# Sheet1.net
KiCad netlist of a schematic drawn in Altium Designer
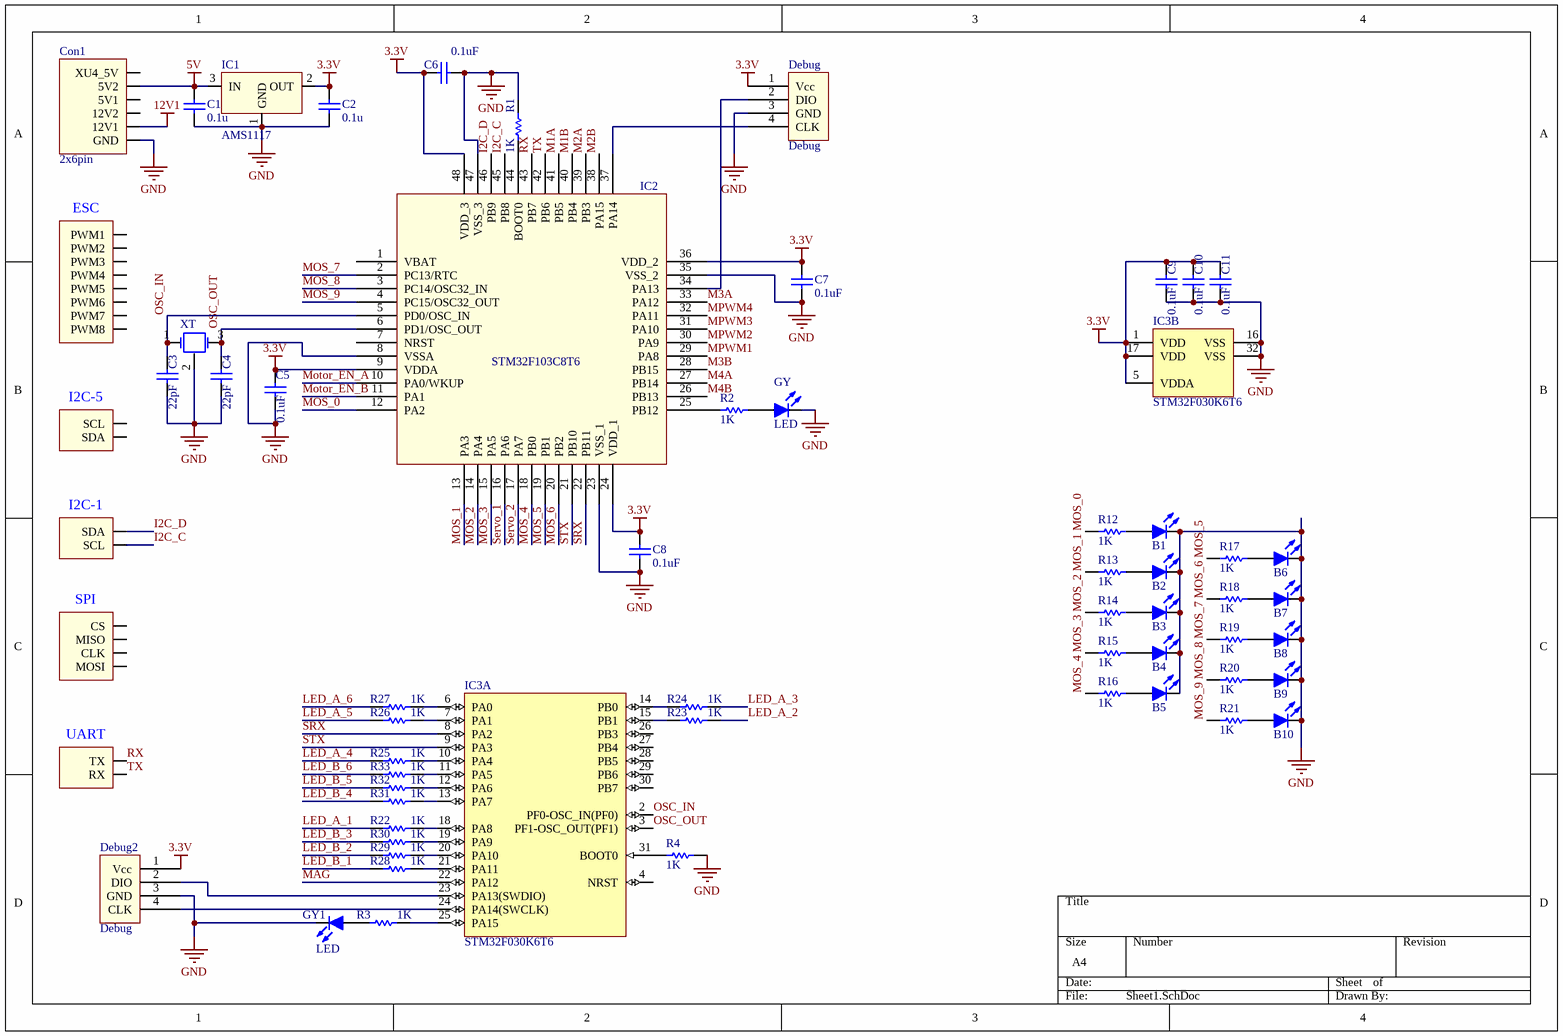
[diagram p0: Sheet1.SchDoc]

(export (version "E")
  (design (tool "Eeschema 10.0.6"))
  (components
    (comp (ref "B1") (value "LED") (footprint "LED-0805") (libsource (lib "MyOwnSchlib_ver1.2") (part "LED")))
    (comp (ref "B2") (value "LED") (footprint "LED-0805") (libsource (lib "MyOwnSchlib_ver1.2") (part "LED")))
    (comp (ref "B3") (value "LED") (footprint "LED-0805") (libsource (lib "MyOwnSchlib_ver1.2") (part "LED")))
    (comp (ref "B4") (value "LED") (footprint "LED-0805") (libsource (lib "MyOwnSchlib_ver1.2") (part "LED")))
    (comp (ref "B5") (value "LED") (footprint "LED-0805") (libsource (lib "MyOwnSchlib_ver1.2") (part "LED")))
    (comp (ref "B6") (value "LED") (footprint "LED-0805") (libsource (lib "MyOwnSchlib_ver1.2") (part "LED")))
    (comp (ref "B7") (value "LED") (footprint "LED-0805") (libsource (lib "MyOwnSchlib_ver1.2") (part "LED")))
    (comp (ref "B8") (value "LED") (footprint "LED-0805") (libsource (lib "MyOwnSchlib_ver1.2") (part "LED")))
    (comp (ref "B9") (value "LED") (footprint "LED-0805") (libsource (lib "MyOwnSchlib_ver1.2") (part "LED")))
    (comp (ref "B10")
      (value "LED")
      (footprint "LED-0805")
      (libsource (lib "MyOwnSchlib_ver1.2") (part "LED"))
    )
    (comp (ref "C1") (value "0.1u") (footprint "C0805") (libsource (lib "MyOwnSchlib_ver1.2") (part "Cap")))
    (comp (ref "C2") (value "0.1u") (footprint "C0805") (libsource (lib "MyOwnSchlib_ver1.2") (part "Cap")))
    (comp (ref "C3") (value "22pF") (footprint "C0805") (libsource (lib "Schlib2") (part "Capacitor")))
    (comp (ref "C4") (value "22pF") (footprint "C0805") (libsource (lib "Schlib2") (part "Capacitor")))
    (comp (ref "C5") (value "0.1uF") (footprint "C0805") (libsource (lib "Schlib2") (part "Capacitor")))
    (comp (ref "C6") (value "0.1uF") (footprint "C0805") (libsource (lib "Schlib2") (part "Capacitor")))
    (comp (ref "C7") (value "0.1uF") (footprint "C0805") (libsource (lib "Schlib2") (part "Capacitor")))
    (comp (ref "C8") (value "0.1uF") (footprint "C0805") (libsource (lib "Schlib2") (part "Capacitor")))
    (comp (ref "C9") (value "0.1uF") (footprint "C0805") (libsource (lib "MyOwnSchlib_ver1.2") (part "Cap")))
    (comp (ref "C10") (value "0.1uF") (footprint "C0805") (libsource (lib "MyOwnSchlib_ver1.2") (part "Cap")))
    (comp (ref "C11") (value "0.1uF") (footprint "C0805") (libsource (lib "MyOwnSchlib_ver1.2") (part "Cap")))
    (comp (ref "Con1") (value "2x6pin") (footprint "2x6pin") (libsource (lib "Schlib1") (part "2x6pin")))
    (comp (ref "Con2") (value "2x10pin") (footprint "2x10pin") (libsource (lib "Schlib1") (part "2x10pin")))
    (comp (ref "Debug")
      (value "Debug")
      (footprint "Debug_SMD")
      (libsource (lib "MyOwnSchlib_ver1.2") (part "Debug"))
    )
    (comp (ref "Debug2") (value "Debug") (footprint "Debug_SMD") (libsource (lib "") (part "Debug_1")))
    (comp (ref "GY") (value "LED") (footprint "LED-0805") (libsource (lib "MyOwnSchlib_ver1.2") (part "LED")))
    (comp (ref "GY1")
      (value "LED")
      (footprint "LED-0805")
      (libsource (lib "MyOwnSchlib_ver1.2") (part "LED"))
    )
    (comp (ref "IC1")
      (value "AMS1117")
      (footprint "SOT-223")
      (libsource (lib "MyOwnSchlib_ver1.2") (part "AMS1117"))
    )
    (comp (ref "IC2")
      (value "STM32F103C8T6")
      (footprint "LQFP48")
      (libsource (lib "Schlib2") (part "STM32F103C8T6"))
    )
    (comp (ref "IC3")
      (value "STM32F030K6T6")
      (footprint "LQFP-32")
      (libsource (lib "STMicroelectronics STM32 F0") (part "STM32F030K6T6"))
    )
    (comp (ref "R1") (value "1K") (footprint "R0805") (libsource (lib "Schlib2") (part "Resistor")))
    (comp (ref "R2")
      (value "1K")
      (footprint "R0805")
      (libsource (lib "MyOwnSchlib_ver1.2") (part "Resistor"))
    )
    (comp (ref "R3")
      (value "1K")
      (footprint "R0805")
      (libsource (lib "MyOwnSchlib_ver1.2") (part "Resistor"))
    )
    (comp (ref "R4")
      (value "1K")
      (footprint "R0805")
      (libsource (lib "MyOwnSchlib_ver1.2") (part "Resistor"))
    )
    (comp (ref "R12")
      (value "1K")
      (footprint "R0805")
      (libsource (lib "MyOwnSchlib_ver1.2") (part "Resistor"))
    )
    (comp (ref "R13")
      (value "1K")
      (footprint "R0805")
      (libsource (lib "MyOwnSchlib_ver1.2") (part "Resistor"))
    )
    (comp (ref "R14")
      (value "1K")
      (footprint "R0805")
      (libsource (lib "MyOwnSchlib_ver1.2") (part "Resistor"))
    )
    (comp (ref "R15")
      (value "1K")
      (footprint "R0805")
      (libsource (lib "MyOwnSchlib_ver1.2") (part "Resistor"))
    )
    (comp (ref "R16")
      (value "1K")
      (footprint "R0805")
      (libsource (lib "MyOwnSchlib_ver1.2") (part "Resistor"))
    )
    (comp (ref "R17")
      (value "1K")
      (footprint "R0805")
      (libsource (lib "MyOwnSchlib_ver1.2") (part "Resistor"))
    )
    (comp (ref "R18")
      (value "1K")
      (footprint "R0805")
      (libsource (lib "MyOwnSchlib_ver1.2") (part "Resistor"))
    )
    (comp (ref "R19")
      (value "1K")
      (footprint "R0805")
      (libsource (lib "MyOwnSchlib_ver1.2") (part "Resistor"))
    )
    (comp (ref "R20")
      (value "1K")
      (footprint "R0805")
      (libsource (lib "MyOwnSchlib_ver1.2") (part "Resistor"))
    )
    (comp (ref "R21")
      (value "1K")
      (footprint "R0805")
      (libsource (lib "MyOwnSchlib_ver1.2") (part "Resistor"))
    )
    (comp (ref "R22")
      (value "1K")
      (footprint "R0805")
      (libsource (lib "MyOwnSchlib_ver1.2") (part "Resistor"))
    )
    (comp (ref "R23")
      (value "1K")
      (footprint "R0805")
      (libsource (lib "MyOwnSchlib_ver1.2") (part "Resistor"))
    )
    (comp (ref "R24")
      (value "1K")
      (footprint "R0805")
      (libsource (lib "MyOwnSchlib_ver1.2") (part "Resistor"))
    )
    (comp (ref "R25")
      (value "1K")
      (footprint "R0805")
      (libsource (lib "MyOwnSchlib_ver1.2") (part "Resistor"))
    )
    (comp (ref "R26")
      (value "1K")
      (footprint "R0805")
      (libsource (lib "MyOwnSchlib_ver1.2") (part "Resistor"))
    )
    (comp (ref "R27")
      (value "1K")
      (footprint "R0805")
      (libsource (lib "MyOwnSchlib_ver1.2") (part "Resistor"))
    )
    (comp (ref "R28")
      (value "1K")
      (footprint "R0805")
      (libsource (lib "MyOwnSchlib_ver1.2") (part "Resistor"))
    )
    (comp (ref "R29")
      (value "1K")
      (footprint "R0805")
      (libsource (lib "MyOwnSchlib_ver1.2") (part "Resistor"))
    )
    (comp (ref "R30")
      (value "1K")
      (footprint "R0805")
      (libsource (lib "MyOwnSchlib_ver1.2") (part "Resistor"))
    )
    (comp (ref "R31")
      (value "1K")
      (footprint "R0805")
      (libsource (lib "MyOwnSchlib_ver1.2") (part "Resistor"))
    )
    (comp (ref "R32")
      (value "1K")
      (footprint "R0805")
      (libsource (lib "MyOwnSchlib_ver1.2") (part "Resistor"))
    )
    (comp (ref "R33")
      (value "1K")
      (footprint "R0805")
      (libsource (lib "MyOwnSchlib_ver1.2") (part "Resistor"))
    )
    (comp (ref "XT") (value "8MHz") (footprint "3225-P") (libsource (lib "Schlib2") (part "Passive Crystal")))
  )
  (nets
    (net (code "1") (name "/I2C_C") (class "Default")
      (node (ref "Con2") (pin "14") (pinfunction "SCL_14") (pintype "passive"))
      (node (ref "IC2") (pin "45") (pinfunction "PB8_45") (pintype "passive"))
    )
    (net (code "2") (name "/I2C_D") (class "Default")
      (node (ref "Con2") (pin "13") (pinfunction "SDA_13") (pintype "passive"))
      (node (ref "IC2") (pin "46") (pinfunction "PB9_46") (pintype "passive"))
    )
    (net (code "3") (name "/LED_A_1") (class "Default")
      (node (ref "R22") (pin "1") (pinfunction "1_1") (pintype "passive"))
    )
    (net (code "4") (name "/LED_A_2") (class "Default")
      (node (ref "R23") (pin "2") (pinfunction "2_2") (pintype "passive"))
    )
    (net (code "5") (name "/LED_A_3") (class "Default")
      (node (ref "R24") (pin "2") (pinfunction "2_2") (pintype "passive"))
    )
    (net (code "6") (name "/LED_A_4") (class "Default")
      (node (ref "R25") (pin "1") (pinfunction "1_1") (pintype "passive"))
    )
    (net (code "7") (name "/LED_A_5") (class "Default")
      (node (ref "R26") (pin "1") (pinfunction "1_1") (pintype "passive"))
    )
    (net (code "8") (name "/LED_A_6") (class "Default")
      (node (ref "R27") (pin "1") (pinfunction "1_1") (pintype "passive"))
    )
    (net (code "9") (name "/LED_B_1") (class "Default")
      (node (ref "R28") (pin "1") (pinfunction "1_1") (pintype "passive"))
    )
    (net (code "10") (name "/LED_B_2") (class "Default")
      (node (ref "R29") (pin "1") (pinfunction "1_1") (pintype "passive"))
    )
    (net (code "11") (name "/LED_B_3") (class "Default")
      (node (ref "R30") (pin "1") (pinfunction "1_1") (pintype "passive"))
    )
    (net (code "12") (name "/LED_B_4") (class "Default")
      (node (ref "R31") (pin "1") (pinfunction "1_1") (pintype "passive"))
    )
    (net (code "13") (name "/LED_B_5") (class "Default")
      (node (ref "R32") (pin "1") (pinfunction "1_1") (pintype "passive"))
    )
    (net (code "14") (name "/LED_B_6") (class "Default")
      (node (ref "R33") (pin "1") (pinfunction "1_1") (pintype "passive"))
    )
    (net (code "15") (name "/M1A") (class "Default")
      (node (ref "IC2") (pin "41") (pinfunction "PB5_41") (pintype "passive"))
    )
    (net (code "16") (name "/M1B") (class "Default")
      (node (ref "IC2") (pin "40") (pinfunction "PB4_40") (pintype "passive"))
    )
    (net (code "17") (name "/M2A") (class "Default")
      (node (ref "IC2") (pin "39") (pinfunction "PB3_39") (pintype "passive"))
    )
    (net (code "18") (name "/M2B") (class "Default")
      (node (ref "IC2") (pin "38") (pinfunction "PA15_38") (pintype "passive"))
    )
    (net (code "19") (name "/M3A") (class "Default")
      (node (ref "IC2") (pin "33") (pinfunction "PA12_33") (pintype "passive"))
    )
    (net (code "20") (name "/M3B") (class "Default")
      (node (ref "IC2") (pin "28") (pinfunction "PB15_28") (pintype "passive"))
    )
    (net (code "21") (name "/M4A") (class "Default")
      (node (ref "IC2") (pin "27") (pinfunction "PB14_27") (pintype "passive"))
    )
    (net (code "22") (name "/M4B") (class "Default")
      (node (ref "IC2") (pin "26") (pinfunction "PB13_26") (pintype "passive"))
    )
    (net (code "23") (name "/MAG") (class "Default")
      (node (ref "IC3") (pin "22") (pinfunction "PA12_22") (pintype "bidirectional"))
    )
    (net (code "24") (name "/MOS_0") (class "Default")
      (node (ref "IC2") (pin "12") (pinfunction "PA2_12") (pintype "passive"))
      (node (ref "R12") (pin "1") (pinfunction "1_1") (pintype "passive"))
    )
    (net (code "25") (name "/MOS_1") (class "Default")
      (node (ref "IC2") (pin "13") (pinfunction "PA3_13") (pintype "passive"))
      (node (ref "R13") (pin "1") (pinfunction "1_1") (pintype "passive"))
    )
    (net (code "26") (name "/MOS_2") (class "Default")
      (node (ref "IC2") (pin "14") (pinfunction "PA4_14") (pintype "passive"))
      (node (ref "R14") (pin "1") (pinfunction "1_1") (pintype "passive"))
    )
    (net (code "27") (name "/MOS_3") (class "Default")
      (node (ref "IC2") (pin "15") (pinfunction "PA5_15") (pintype "passive"))
      (node (ref "R15") (pin "1") (pinfunction "1_1") (pintype "passive"))
    )
    (net (code "28") (name "/MOS_4") (class "Default")
      (node (ref "IC2") (pin "18") (pinfunction "PB0_18") (pintype "passive"))
      (node (ref "R16") (pin "1") (pinfunction "1_1") (pintype "passive"))
    )
    (net (code "29") (name "/MOS_5") (class "Default")
      (node (ref "IC2") (pin "19") (pinfunction "PB1_19") (pintype "passive"))
      (node (ref "R17") (pin "1") (pinfunction "1_1") (pintype "passive"))
    )
    (net (code "30") (name "/MOS_6") (class "Default")
      (node (ref "IC2") (pin "20") (pinfunction "PB2_20") (pintype "passive"))
      (node (ref "R18") (pin "1") (pinfunction "1_1") (pintype "passive"))
    )
    (net (code "31") (name "/MOS_7") (class "Default")
      (node (ref "IC2") (pin "2") (pinfunction "PC13/RTC_2") (pintype "passive"))
      (node (ref "R19") (pin "1") (pinfunction "1_1") (pintype "passive"))
    )
    (net (code "32") (name "/MOS_8") (class "Default")
      (node (ref "IC2") (pin "3") (pinfunction "PC14/OSC32_IN_3") (pintype "passive"))
      (node (ref "R20") (pin "1") (pinfunction "1_1") (pintype "passive"))
    )
    (net (code "33") (name "/MOS_9") (class "Default")
      (node (ref "IC2") (pin "4") (pinfunction "PC15/OSC32_OUT_4") (pintype "passive"))
      (node (ref "R21") (pin "1") (pinfunction "1_1") (pintype "passive"))
    )
    (net (code "34") (name "/MPWM1") (class "Default")
      (node (ref "IC2") (pin "29") (pinfunction "PA8_29") (pintype "passive"))
    )
    (net (code "35") (name "/MPWM2") (class "Default")
      (node (ref "IC2") (pin "30") (pinfunction "PA9_30") (pintype "passive"))
    )
    (net (code "36") (name "/MPWM3") (class "Default")
      (node (ref "IC2") (pin "31") (pinfunction "PA10_31") (pintype "passive"))
    )
    (net (code "37") (name "/MPWM4") (class "Default")
      (node (ref "IC2") (pin "32") (pinfunction "PA11_32") (pintype "passive"))
    )
    (net (code "38") (name "/Motor_EN_A") (class "Default")
      (node (ref "IC2") (pin "10") (pinfunction "PA0/WKUP_10") (pintype "passive"))
    )
    (net (code "39") (name "/Motor_EN_B") (class "Default")
      (node (ref "IC2") (pin "11") (pinfunction "PA1_11") (pintype "passive"))
    )
    (net (code "40") (name "/OSC_IN") (class "Default")
      (node (ref "C3") (pin "1") (pinfunction "1_1") (pintype "passive"))
      (node (ref "IC2") (pin "5") (pinfunction "PD0/OSC_IN_5") (pintype "passive"))
      (node (ref "IC3") (pin "2") (pinfunction "PF0-OSC_IN(PF0)_2") (pintype "bidirectional"))
      (node (ref "XT") (pin "1") (pinfunction "OSC1_1") (pintype "passive"))
    )
    (net (code "41") (name "/OSC_OUT") (class "Default")
      (node (ref "C4") (pin "1") (pinfunction "1_1") (pintype "passive"))
      (node (ref "IC2") (pin "6") (pinfunction "PD1/OSC_OUT_6") (pintype "passive"))
      (node (ref "IC3") (pin "3") (pinfunction "PF1-OSC_OUT(PF1)_3") (pintype "bidirectional"))
      (node (ref "XT") (pin "3") (pinfunction "OSC2_3") (pintype "passive"))
    )
    (net (code "42") (name "/RX") (class "Default")
      (node (ref "Con2") (pin "19") (pinfunction "TX_19") (pintype "passive"))
      (node (ref "IC2") (pin "43") (pinfunction "PB7_43") (pintype "passive"))
    )
    (net (code "43") (name "/SRX") (class "Default")
      (node (ref "IC2") (pin "22") (pinfunction "PB11_22") (pintype "passive"))
      (node (ref "IC3") (pin "8") (pinfunction "PA2_8") (pintype "bidirectional"))
    )
    (net (code "44") (name "/STX") (class "Default")
      (node (ref "IC2") (pin "21") (pinfunction "PB10_21") (pintype "passive"))
      (node (ref "IC3") (pin "9") (pinfunction "PA3_9") (pintype "bidirectional"))
    )
    (net (code "45") (name "/Servo_1") (class "Default")
      (node (ref "IC2") (pin "16") (pinfunction "PA6_16") (pintype "passive"))
    )
    (net (code "46") (name "/Servo_2") (class "Default")
      (node (ref "IC2") (pin "17") (pinfunction "PA7_17") (pintype "passive"))
    )
    (net (code "47") (name "/TX") (class "Default")
      (node (ref "Con2") (pin "20") (pinfunction "RX_20") (pintype "passive"))
      (node (ref "IC2") (pin "42") (pinfunction "PB6_42") (pintype "passive"))
    )
    (net (code "48") (name "3.3V") (class "Default")
      (node (ref "C10") (pin "2") (pinfunction "2_2") (pintype "passive"))
      (node (ref "C11") (pin "2") (pinfunction "2_2") (pintype "passive"))
      (node (ref "C2") (pin "2") (pinfunction "2_2") (pintype "passive"))
      (node (ref "C5") (pin "2") (pinfunction "2_2") (pintype "passive"))
      (node (ref "C6") (pin "1") (pinfunction "1_1") (pintype "passive"))
      (node (ref "C7") (pin "2") (pinfunction "2_2") (pintype "passive"))
      (node (ref "C8") (pin "2") (pinfunction "2_2") (pintype "passive"))
      (node (ref "C9") (pin "2") (pinfunction "2_2") (pintype "passive"))
      (node (ref "Debug") (pin "1") (pinfunction "Vcc_1") (pintype "passive"))
      (node (ref "Debug2") (pin "1") (pinfunction "Vcc_1") (pintype "passive"))
      (node (ref "IC1") (pin "2") (pinfunction "OUT_2") (pintype "passive"))
      (node (ref "IC2") (pin "24") (pinfunction "VDD_1_24") (pintype "passive"))
      (node (ref "IC2") (pin "36") (pinfunction "VDD_2_36") (pintype "passive"))
      (node (ref "IC2") (pin "48") (pinfunction "VDD_3_48") (pintype "passive"))
      (node (ref "IC2") (pin "9") (pinfunction "VDDA_9") (pintype "passive"))
      (node (ref "IC3") (pin "1") (pinfunction "VDD_1") (pintype "power_in"))
      (node (ref "IC3") (pin "17") (pinfunction "VDD_17") (pintype "power_in"))
      (node (ref "IC3") (pin "5") (pinfunction "VDDA_5") (pintype "power_in"))
    )
    (net (code "49") (name "5V") (class "Default")
      (node (ref "C1") (pin "2") (pinfunction "2_2") (pintype "passive"))
      (node (ref "Con1") (pin "2") (pinfunction "5V2_2") (pintype "passive"))
      (node (ref "IC1") (pin "3") (pinfunction "IN_3") (pintype "passive"))
    )
    (net (code "50") (name "12V1") (class "Default")
      (node (ref "Con1") (pin "5") (pinfunction "12V1_5") (pintype "passive"))
    )
    (net (code "51") (name "GND") (class "Default")
      (node (ref "B1") (pin "2") (pinfunction "K_2") (pintype "passive"))
      (node (ref "B10") (pin "2") (pinfunction "K_2") (pintype "passive"))
      (node (ref "B2") (pin "2") (pinfunction "K_2") (pintype "passive"))
      (node (ref "B3") (pin "2") (pinfunction "K_2") (pintype "passive"))
      (node (ref "B4") (pin "2") (pinfunction "K_2") (pintype "passive"))
      (node (ref "B5") (pin "2") (pinfunction "K_2") (pintype "passive"))
      (node (ref "B6") (pin "2") (pinfunction "K_2") (pintype "passive"))
      (node (ref "B7") (pin "2") (pinfunction "K_2") (pintype "passive"))
      (node (ref "B8") (pin "2") (pinfunction "K_2") (pintype "passive"))
      (node (ref "B9") (pin "2") (pinfunction "K_2") (pintype "passive"))
      (node (ref "C1") (pin "1") (pinfunction "1_1") (pintype "passive"))
      (node (ref "C10") (pin "1") (pinfunction "1_1") (pintype "passive"))
      (node (ref "C11") (pin "1") (pinfunction "1_1") (pintype "passive"))
      (node (ref "C2") (pin "1") (pinfunction "1_1") (pintype "passive"))
      (node (ref "C3") (pin "2") (pinfunction "2_2") (pintype "passive"))
      (node (ref "C4") (pin "2") (pinfunction "2_2") (pintype "passive"))
      (node (ref "C5") (pin "1") (pinfunction "1_1") (pintype "passive"))
      (node (ref "C6") (pin "2") (pinfunction "2_2") (pintype "passive"))
      (node (ref "C7") (pin "1") (pinfunction "1_1") (pintype "passive"))
      (node (ref "C8") (pin "1") (pinfunction "1_1") (pintype "passive"))
      (node (ref "C9") (pin "1") (pinfunction "1_1") (pintype "passive"))
      (node (ref "Con1") (pin "6") (pinfunction "GND_6") (pintype "passive"))
      (node (ref "Debug") (pin "3") (pinfunction "GND_3") (pintype "passive"))
      (node (ref "Debug2") (pin "3") (pinfunction "GND_3") (pintype "passive"))
      (node (ref "GY") (pin "2") (pinfunction "K_2") (pintype "passive"))
      (node (ref "GY1") (pin "2") (pinfunction "K_2") (pintype "passive"))
      (node (ref "IC1") (pin "1") (pinfunction "GND_1") (pintype "passive"))
      (node (ref "IC2") (pin "23") (pinfunction "VSS_1_23") (pintype "passive"))
      (node (ref "IC2") (pin "35") (pinfunction "VSS_2_35") (pintype "passive"))
      (node (ref "IC2") (pin "47") (pinfunction "VSS_3_47") (pintype "passive"))
      (node (ref "IC2") (pin "8") (pinfunction "VSSA_8") (pintype "passive"))
      (node (ref "IC3") (pin "16") (pinfunction "VSS_16") (pintype "power_in"))
      (node (ref "IC3") (pin "32") (pinfunction "VSS_32") (pintype "power_in"))
      (node (ref "R1") (pin "2") (pinfunction "2_2") (pintype "passive"))
      (node (ref "R4") (pin "2") (pinfunction "2_2") (pintype "passive"))
      (node (ref "XT") (pin "2") (pinfunction "2_2") (pintype "passive"))
    )
    (net (code "52") (name "Net-(B1-A)") (class "Default")
      (node (ref "B1") (pin "1") (pinfunction "A_1") (pintype "passive"))
      (node (ref "R12") (pin "2") (pinfunction "2_2") (pintype "passive"))
    )
    (net (code "53") (name "Net-(B2-A)") (class "Default")
      (node (ref "B2") (pin "1") (pinfunction "A_1") (pintype "passive"))
      (node (ref "R13") (pin "2") (pinfunction "2_2") (pintype "passive"))
    )
    (net (code "54") (name "Net-(B3-A)") (class "Default")
      (node (ref "B3") (pin "1") (pinfunction "A_1") (pintype "passive"))
      (node (ref "R14") (pin "2") (pinfunction "2_2") (pintype "passive"))
    )
    (net (code "55") (name "Net-(B4-A)") (class "Default")
      (node (ref "B4") (pin "1") (pinfunction "A_1") (pintype "passive"))
      (node (ref "R15") (pin "2") (pinfunction "2_2") (pintype "passive"))
    )
    (net (code "56") (name "Net-(B5-A)") (class "Default")
      (node (ref "B5") (pin "1") (pinfunction "A_1") (pintype "passive"))
      (node (ref "R16") (pin "2") (pinfunction "2_2") (pintype "passive"))
    )
    (net (code "57") (name "Net-(B6-A)") (class "Default")
      (node (ref "B6") (pin "1") (pinfunction "A_1") (pintype "passive"))
      (node (ref "R17") (pin "2") (pinfunction "2_2") (pintype "passive"))
    )
    (net (code "58") (name "Net-(B7-A)") (class "Default")
      (node (ref "B7") (pin "1") (pinfunction "A_1") (pintype "passive"))
      (node (ref "R18") (pin "2") (pinfunction "2_2") (pintype "passive"))
    )
    (net (code "59") (name "Net-(B8-A)") (class "Default")
      (node (ref "B8") (pin "1") (pinfunction "A_1") (pintype "passive"))
      (node (ref "R19") (pin "2") (pinfunction "2_2") (pintype "passive"))
    )
    (net (code "60") (name "Net-(B9-A)") (class "Default")
      (node (ref "B9") (pin "1") (pinfunction "A_1") (pintype "passive"))
      (node (ref "R20") (pin "2") (pinfunction "2_2") (pintype "passive"))
    )
    (net (code "61") (name "Net-(B10-A)") (class "Default")
      (node (ref "B10") (pin "1") (pinfunction "A_1") (pintype "passive"))
      (node (ref "R21") (pin "2") (pinfunction "2_2") (pintype "passive"))
    )
    (net (code "62") (name "Net-(Debug-CLK)") (class "Default")
      (node (ref "Debug") (pin "4") (pinfunction "CLK_4") (pintype "passive"))
      (node (ref "IC2") (pin "37") (pinfunction "PA14_37") (pintype "passive"))
    )
    (net (code "63") (name "Net-(Debug-DIO)") (class "Default")
      (node (ref "Debug") (pin "2") (pinfunction "DIO_2") (pintype "passive"))
      (node (ref "IC2") (pin "34") (pinfunction "PA13_34") (pintype "passive"))
    )
    (net (code "64") (name "Net-(Debug2-CLK)") (class "Default")
      (node (ref "Debug2") (pin "4") (pinfunction "CLK_4") (pintype "passive"))
      (node (ref "IC3") (pin "24") (pinfunction "PA14(SWCLK)_24") (pintype "bidirectional"))
    )
    (net (code "65") (name "Net-(Debug2-DIO)") (class "Default")
      (node (ref "Debug2") (pin "2") (pinfunction "DIO_2") (pintype "passive"))
      (node (ref "IC3") (pin "23") (pinfunction "PA13(SWDIO)_23") (pintype "bidirectional"))
    )
    (net (code "66") (name "Net-(GY-A)") (class "Default")
      (node (ref "GY") (pin "1") (pinfunction "A_1") (pintype "passive"))
      (node (ref "R2") (pin "2") (pinfunction "2_2") (pintype "passive"))
    )
    (net (code "67") (name "Net-(GY1-A)") (class "Default")
      (node (ref "GY1") (pin "1") (pinfunction "A_1") (pintype "passive"))
      (node (ref "R3") (pin "1") (pinfunction "1_1") (pintype "passive"))
    )
    (net (code "68") (name "Net-(IC2-BOOT0)") (class "Default")
      (node (ref "IC2") (pin "44") (pinfunction "BOOT0_44") (pintype "passive"))
      (node (ref "R1") (pin "1") (pinfunction "1_1") (pintype "passive"))
    )
    (net (code "69") (name "Net-(IC2-PB12)") (class "Default")
      (node (ref "IC2") (pin "25") (pinfunction "PB12_25") (pintype "passive"))
      (node (ref "R2") (pin "1") (pinfunction "1_1") (pintype "passive"))
    )
    (net (code "70") (name "Net-(IC3A-BOOT0)") (class "Default")
      (node (ref "IC3") (pin "31") (pinfunction "BOOT0_31") (pintype "input"))
      (node (ref "R4") (pin "1") (pinfunction "1_1") (pintype "passive"))
    )
    (net (code "71") (name "Net-(IC3A-PA0)") (class "Default")
      (node (ref "IC3") (pin "6") (pinfunction "PA0_6") (pintype "bidirectional"))
      (node (ref "R27") (pin "2") (pinfunction "2_2") (pintype "passive"))
    )
    (net (code "72") (name "Net-(IC3A-PA1)") (class "Default")
      (node (ref "IC3") (pin "7") (pinfunction "PA1_7") (pintype "bidirectional"))
      (node (ref "R26") (pin "2") (pinfunction "2_2") (pintype "passive"))
    )
    (net (code "73") (name "Net-(IC3A-PA4)") (class "Default")
      (node (ref "IC3") (pin "10") (pinfunction "PA4_10") (pintype "bidirectional"))
      (node (ref "R25") (pin "2") (pinfunction "2_2") (pintype "passive"))
    )
    (net (code "74") (name "Net-(IC3A-PA5)") (class "Default")
      (node (ref "IC3") (pin "11") (pinfunction "PA5_11") (pintype "bidirectional"))
      (node (ref "R33") (pin "2") (pinfunction "2_2") (pintype "passive"))
    )
    (net (code "75") (name "Net-(IC3A-PA6)") (class "Default")
      (node (ref "IC3") (pin "12") (pinfunction "PA6_12") (pintype "bidirectional"))
      (node (ref "R32") (pin "2") (pinfunction "2_2") (pintype "passive"))
    )
    (net (code "76") (name "Net-(IC3A-PA7)") (class "Default")
      (node (ref "IC3") (pin "13") (pinfunction "PA7_13") (pintype "bidirectional"))
      (node (ref "R31") (pin "2") (pinfunction "2_2") (pintype "passive"))
    )
    (net (code "77") (name "Net-(IC3A-PA8)") (class "Default")
      (node (ref "IC3") (pin "18") (pinfunction "PA8_18") (pintype "bidirectional"))
      (node (ref "R22") (pin "2") (pinfunction "2_2") (pintype "passive"))
    )
    (net (code "78") (name "Net-(IC3A-PA9)") (class "Default")
      (node (ref "IC3") (pin "19") (pinfunction "PA9_19") (pintype "bidirectional"))
      (node (ref "R30") (pin "2") (pinfunction "2_2") (pintype "passive"))
    )
    (net (code "79") (name "Net-(IC3A-PA10)") (class "Default")
      (node (ref "IC3") (pin "20") (pinfunction "PA10_20") (pintype "bidirectional"))
      (node (ref "R29") (pin "2") (pinfunction "2_2") (pintype "passive"))
    )
    (net (code "80") (name "Net-(IC3A-PA11)") (class "Default")
      (node (ref "IC3") (pin "21") (pinfunction "PA11_21") (pintype "bidirectional"))
      (node (ref "R28") (pin "2") (pinfunction "2_2") (pintype "passive"))
    )
    (net (code "81") (name "Net-(IC3A-PA15)") (class "Default")
      (node (ref "IC3") (pin "25") (pinfunction "PA15_25") (pintype "bidirectional"))
      (node (ref "R3") (pin "2") (pinfunction "2_2") (pintype "passive"))
    )
    (net (code "82") (name "Net-(IC3A-PB0)") (class "Default")
      (node (ref "IC3") (pin "14") (pinfunction "PB0_14") (pintype "bidirectional"))
      (node (ref "R24") (pin "1") (pinfunction "1_1") (pintype "passive"))
    )
    (net (code "83") (name "Net-(IC3A-PB1)") (class "Default")
      (node (ref "IC3") (pin "15") (pinfunction "PB1_15") (pintype "bidirectional"))
      (node (ref "R23") (pin "1") (pinfunction "1_1") (pintype "passive"))
    )
    (net (code "84") (name "unconnected-(Con1-5V1-Pad3)") (class "Default")
      (node (ref "Con1") (pin "3") (pinfunction "5V1_3") (pintype "passive"))
    )
    (net (code "85") (name "unconnected-(Con1-12V2-Pad4)") (class "Default")
      (node (ref "Con1") (pin "4") (pinfunction "12V2_4") (pintype "passive"))
    )
    (net (code "86") (name "unconnected-(Con1-XU4_5V-Pad1)") (class "Default")
      (node (ref "Con1") (pin "1") (pinfunction "XU4_5V_1") (pintype "passive"))
    )
    (net (code "87") (name "unconnected-(Con2A-PWM1-Pad1)") (class "Default")
      (node (ref "Con2") (pin "1") (pinfunction "PWM1_1") (pintype "passive"))
    )
    (net (code "88") (name "unconnected-(Con2A-PWM2-Pad2)") (class "Default")
      (node (ref "Con2") (pin "2") (pinfunction "PWM2_2") (pintype "passive"))
    )
    (net (code "89") (name "unconnected-(Con2A-PWM3-Pad3)") (class "Default")
      (node (ref "Con2") (pin "3") (pinfunction "PWM3_3") (pintype "passive"))
    )
    (net (code "90") (name "unconnected-(Con2A-PWM4-Pad4)") (class "Default")
      (node (ref "Con2") (pin "4") (pinfunction "PWM4_4") (pintype "passive"))
    )
    (net (code "91") (name "unconnected-(Con2A-PWM5-Pad5)") (class "Default")
      (node (ref "Con2") (pin "5") (pinfunction "PWM5_5") (pintype "passive"))
    )
    (net (code "92") (name "unconnected-(Con2A-PWM6-Pad6)") (class "Default")
      (node (ref "Con2") (pin "6") (pinfunction "PWM6_6") (pintype "passive"))
    )
    (net (code "93") (name "unconnected-(Con2A-PWM7-Pad7)") (class "Default")
      (node (ref "Con2") (pin "7") (pinfunction "PWM7_7") (pintype "passive"))
    )
    (net (code "94") (name "unconnected-(Con2A-PWM8-Pad8)") (class "Default")
      (node (ref "Con2") (pin "8") (pinfunction "PWM8_8") (pintype "passive"))
    )
    (net (code "95") (name "unconnected-(Con2B-SCL-Pad11)") (class "Default")
      (node (ref "Con2") (pin "11") (pinfunction "SCL_11") (pintype "passive"))
    )
    (net (code "96") (name "unconnected-(Con2B-SDA-Pad12)") (class "Default")
      (node (ref "Con2") (pin "12") (pinfunction "SDA_12") (pintype "passive"))
    )
    (net (code "97") (name "unconnected-(Con2D-CLK-Pad17)") (class "Default")
      (node (ref "Con2") (pin "17") (pinfunction "CLK_17") (pintype "passive"))
    )
    (net (code "98") (name "unconnected-(Con2D-CS-Pad15)") (class "Default")
      (node (ref "Con2") (pin "15") (pinfunction "CS_15") (pintype "passive"))
    )
    (net (code "99") (name "unconnected-(Con2D-MISO-Pad16)") (class "Default")
      (node (ref "Con2") (pin "16") (pinfunction "MISO_16") (pintype "passive"))
    )
    (net (code "100") (name "unconnected-(Con2D-MOSI-Pad18)") (class "Default")
      (node (ref "Con2") (pin "18") (pinfunction "MOSI_18") (pintype "passive"))
    )
    (net (code "101") (name "unconnected-(IC2-NRST-Pad7)") (class "Default")
      (node (ref "IC2") (pin "7") (pinfunction "NRST_7") (pintype "passive"))
    )
    (net (code "102") (name "unconnected-(IC2-VBAT-Pad1)") (class "Default")
      (node (ref "IC2") (pin "1") (pinfunction "VBAT_1") (pintype "passive"))
    )
    (net (code "103") (name "unconnected-(IC3A-NRST-Pad4)") (class "Default")
      (node (ref "IC3") (pin "4") (pinfunction "NRST_4") (pintype "bidirectional"))
    )
    (net (code "104") (name "unconnected-(IC3A-PB3-Pad26)") (class "Default")
      (node (ref "IC3") (pin "26") (pinfunction "PB3_26") (pintype "bidirectional"))
    )
    (net (code "105") (name "unconnected-(IC3A-PB4-Pad27)") (class "Default")
      (node (ref "IC3") (pin "27") (pinfunction "PB4_27") (pintype "bidirectional"))
    )
    (net (code "106") (name "unconnected-(IC3A-PB5-Pad28)") (class "Default")
      (node (ref "IC3") (pin "28") (pinfunction "PB5_28") (pintype "bidirectional"))
    )
    (net (code "107") (name "unconnected-(IC3A-PB6-Pad29)") (class "Default")
      (node (ref "IC3") (pin "29") (pinfunction "PB6_29") (pintype "bidirectional"))
    )
    (net (code "108") (name "unconnected-(IC3A-PB7-Pad30)") (class "Default")
      (node (ref "IC3") (pin "30") (pinfunction "PB7_30") (pintype "bidirectional"))
    )
  )
)
